# Invictus_R2_Bot.net
KiCad netlist of a schematic drawn in EAGLE
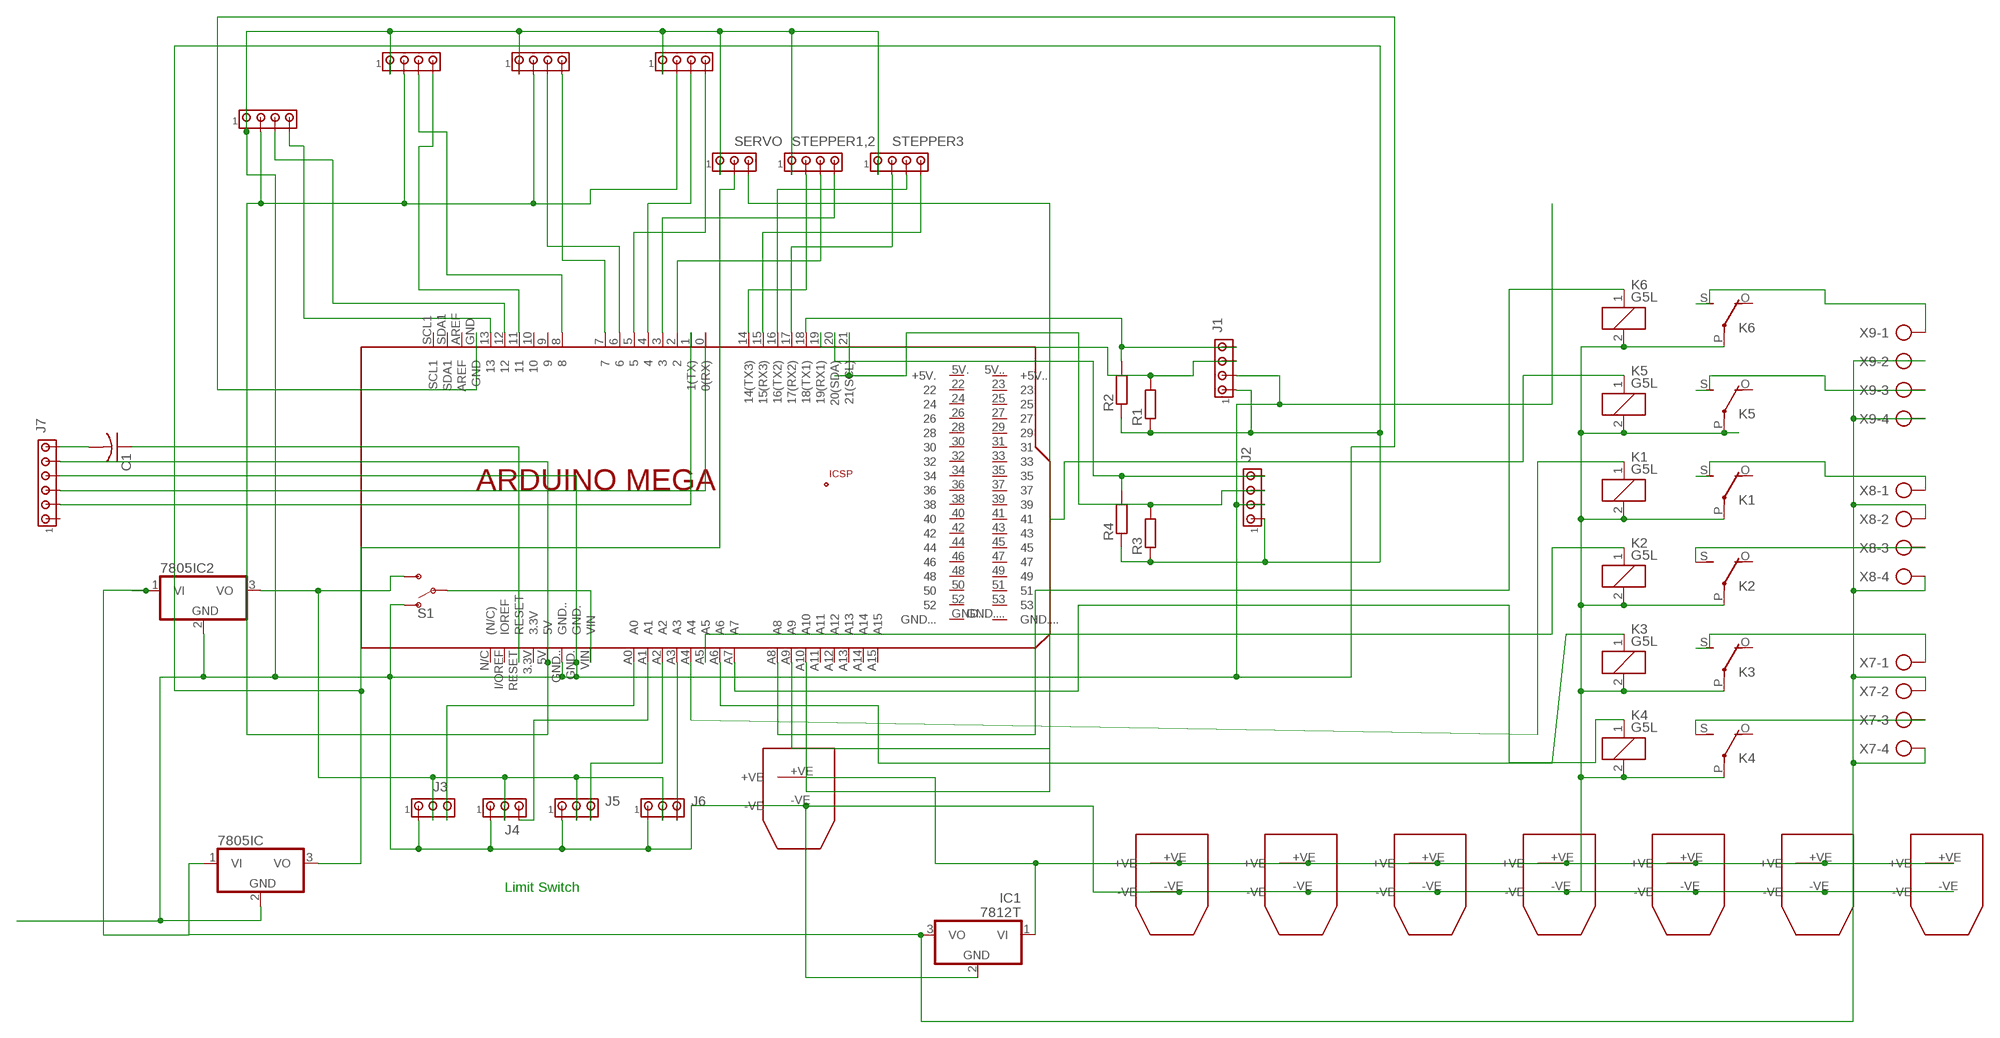
[diagram p0: schematic, sheet 1]

(export (version "E")
  (design (tool "Eeschema 10.0.6"))
  (components
    (comp (ref "7805IC")
      (value "7812T")
      (footprint "eagle-import:TO220H")
      (libsource (lib "eagle-import") (part "78T12"))
    )
    (comp (ref "7805IC2")
      (value "7805T")
      (footprint "eagle-import:TO220H")
      (libsource (lib "eagle-import") (part "78T05"))
    )
    (comp (ref "C1")
      (value "C-US025-030X050")
      (footprint "eagle-import:C025-030X050")
      (libsource (lib "eagle-import") (part "C-US025-030X050"))
    )
    (comp (ref "IC1")
      (value "7812T")
      (footprint "eagle-import:TO220H")
      (libsource (lib "eagle-import") (part "78T12"))
    )
    (comp (ref "J1")
      (value "MTA04-100")
      (footprint "eagle-import:10X04MTA")
      (libsource (lib "eagle-import") (part "MTA04-100"))
    )
    (comp (ref "J2")
      (value "MTA04-100")
      (footprint "eagle-import:10X04MTA")
      (libsource (lib "eagle-import") (part "MTA04-100"))
    )
    (comp (ref "J3")
      (value "MTA03-100")
      (footprint "eagle-import:10X03MTA")
      (libsource (lib "eagle-import") (part "MTA03-100"))
    )
    (comp (ref "J4")
      (value "MTA03-100")
      (footprint "eagle-import:10X03MTA")
      (libsource (lib "eagle-import") (part "MTA03-100"))
    )
    (comp (ref "J5")
      (value "MTA03-100")
      (footprint "eagle-import:10X03MTA")
      (libsource (lib "eagle-import") (part "MTA03-100"))
    )
    (comp (ref "J6")
      (value "MTA03-100")
      (footprint "eagle-import:10X03MTA")
      (libsource (lib "eagle-import") (part "MTA03-100"))
    )
    (comp (ref "J7")
      (value "MTA06-100")
      (footprint "eagle-import:10X06MTA")
      (libsource (lib "eagle-import") (part "MTA06-100"))
    )
    (comp (ref "K1")
      (value "G5L")
      (footprint "eagle-import:G5LE")
      (libsource (lib "eagle-import") (part "G5L"))
    )
    (comp (ref "K2")
      (value "G5L")
      (footprint "eagle-import:G5LE")
      (libsource (lib "eagle-import") (part "G5L"))
    )
    (comp (ref "K3")
      (value "G5L")
      (footprint "eagle-import:G5LE")
      (libsource (lib "eagle-import") (part "G5L"))
    )
    (comp (ref "K4")
      (value "G5L")
      (footprint "eagle-import:G5LE")
      (libsource (lib "eagle-import") (part "G5L"))
    )
    (comp (ref "K5")
      (value "G5L")
      (footprint "eagle-import:G5LE")
      (libsource (lib "eagle-import") (part "G5L"))
    )
    (comp (ref "K6")
      (value "G5L")
      (footprint "eagle-import:G5LE")
      (libsource (lib "eagle-import") (part "G5L"))
    )
    (comp (ref "PCB2")
      (value "ARDUINO_MEGA2560")
      (footprint "eagle-import:ARDUINO_MEGA2560")
      (libsource (lib "eagle-import") (part "ARDUINO_MEGA2560"))
    )
    (comp (ref "R1")
      (value "R-EU_0207/7")
      (footprint "eagle-import:0207_7")
      (libsource (lib "eagle-import") (part "R-EU_0207/7"))
    )
    (comp (ref "R2")
      (value "R-EU_0207/7")
      (footprint "eagle-import:0207_7")
      (libsource (lib "eagle-import") (part "R-EU_0207/7"))
    )
    (comp (ref "R3")
      (value "R-EU_0207/7")
      (footprint "eagle-import:0207_7")
      (libsource (lib "eagle-import") (part "R-EU_0207/7"))
    )
    (comp (ref "R4")
      (value "R-EU_0207/7")
      (footprint "eagle-import:0207_7")
      (libsource (lib "eagle-import") (part "R-EU_0207/7"))
    )
    (comp (ref "S1")
      (value "SWITCH-SPDT-PTH-11.6X4.0MM")
      (footprint "eagle-import:SWITCH_SPDT_PTH_11.6X4.0MM")
      (libsource (lib "eagle-import") (part "SWITCH-SPDT-PTH-11.6X4.0MM"))
    )
    (comp (ref "SERVO")
      (value "MTA03-100")
      (footprint "eagle-import:10X03MTA")
      (libsource (lib "eagle-import") (part "MTA03-100"))
    )
    (comp (ref "STEPPER1,1")
      (value "MTA04-100")
      (footprint "eagle-import:10X04MTA")
      (libsource (lib "eagle-import") (part "MTA04-100"))
    )
    (comp (ref "STEPPER1,2")
      (value "MTA04-100")
      (footprint "eagle-import:10X04MTA")
      (libsource (lib "eagle-import") (part "MTA04-100"))
    )
    (comp (ref "STEPPER1,3")
      (value "MTA04-100")
      (footprint "eagle-import:10X04MTA")
      (libsource (lib "eagle-import") (part "MTA04-100"))
    )
    (comp (ref "STEPPER1,4")
      (value "MTA04-100")
      (footprint "eagle-import:10X04MTA")
      (libsource (lib "eagle-import") (part "MTA04-100"))
    )
    (comp (ref "STEPPER1,5")
      (value "MTA04-100")
      (footprint "eagle-import:10X04MTA")
      (libsource (lib "eagle-import") (part "MTA04-100"))
    )
    (comp (ref "STEPPER3")
      (value "MTA04-100")
      (footprint "eagle-import:10X04MTA")
      (libsource (lib "eagle-import") (part "MTA04-100"))
    )
    (comp (ref "X7")
      (value "AK500/4-H")
      (footprint "eagle-import:AK500_4-H")
      (libsource (lib "eagle-import") (part "AK500/4-H"))
    )
    (comp (ref "X8")
      (value "AK500/4-H")
      (footprint "eagle-import:AK500_4-H")
      (libsource (lib "eagle-import") (part "AK500/4-H"))
    )
    (comp (ref "X9")
      (value "AK500/4-H")
      (footprint "eagle-import:AK500_4-H")
      (libsource (lib "eagle-import") (part "AK500/4-H"))
    )
    (comp (ref "XT1")
      (value "XT60XT60")
      (footprint "eagle-import:XT60")
      (libsource (lib "eagle-import") (part "XT60XT60"))
    )
    (comp (ref "XT2")
      (value "XT60XT60")
      (footprint "eagle-import:XT60")
      (libsource (lib "eagle-import") (part "XT60XT60"))
    )
    (comp (ref "XT3")
      (value "XT60XT60")
      (footprint "eagle-import:XT60")
      (libsource (lib "eagle-import") (part "XT60XT60"))
    )
    (comp (ref "XT4")
      (value "XT60XT60")
      (footprint "eagle-import:XT60")
      (libsource (lib "eagle-import") (part "XT60XT60"))
    )
    (comp (ref "XT5")
      (value "XT60XT60")
      (footprint "eagle-import:XT60")
      (libsource (lib "eagle-import") (part "XT60XT60"))
    )
    (comp (ref "XT6")
      (value "XT60XT60")
      (footprint "eagle-import:XT60")
      (libsource (lib "eagle-import") (part "XT60XT60"))
    )
    (comp (ref "XT7")
      (value "XT60XT60")
      (footprint "eagle-import:XT60")
      (libsource (lib "eagle-import") (part "XT60XT60"))
    )
    (comp (ref "XT60")
      (value "XT60XT60")
      (footprint "eagle-import:XT60")
      (libsource (lib "eagle-import") (part "XT60XT60"))
    )
  )
  (nets
    (net (code "1") (name "Net-(7805IC-GND)") (class "Default")
      (node (ref "7805IC") (pin "2") (pinfunction "GND_2") (pintype "passive"))
      (node (ref "7805IC2") (pin "2") (pinfunction "GND_2") (pintype "passive"))
      (node (ref "IC1") (pin "2") (pinfunction "GND_2") (pintype "passive"))
      (node (ref "J1") (pin "2") (pinfunction "2_2") (pintype "passive"))
      (node (ref "J2") (pin "2") (pinfunction "2_2") (pintype "passive"))
      (node (ref "J3") (pin "1") (pinfunction "1_1") (pintype "passive"))
      (node (ref "J4") (pin "1") (pinfunction "1_1") (pintype "passive"))
      (node (ref "J5") (pin "1") (pinfunction "1_1") (pintype "passive"))
      (node (ref "J6") (pin "1") (pinfunction "1_1") (pintype "passive"))
      (node (ref "J7") (pin "4") (pinfunction "4_4") (pintype "passive"))
      (node (ref "K1") (pin "2") (pinfunction "2_2") (pintype "passive"))
      (node (ref "K1") (pin "P") (pinfunction "P_P") (pintype "passive"))
      (node (ref "K2") (pin "2") (pinfunction "2_2") (pintype "passive"))
      (node (ref "K2") (pin "P") (pinfunction "P_P") (pintype "passive"))
      (node (ref "K3") (pin "2") (pinfunction "2_2") (pintype "passive"))
      (node (ref "K3") (pin "P") (pinfunction "P_P") (pintype "passive"))
      (node (ref "K4") (pin "2") (pinfunction "2_2") (pintype "passive"))
      (node (ref "K4") (pin "P") (pinfunction "P_P") (pintype "passive"))
      (node (ref "K5") (pin "2") (pinfunction "2_2") (pintype "passive"))
      (node (ref "K5") (pin "P") (pinfunction "P_P") (pintype "passive"))
      (node (ref "K6") (pin "2") (pinfunction "2_2") (pintype "passive"))
      (node (ref "K6") (pin "P") (pinfunction "P_P") (pintype "passive"))
      (node (ref "PCB2") (pin "GND") (pinfunction "GND_GND") (pintype "bidirectional"))
      (node (ref "PCB2") (pin "GND.") (pinfunction "GND._GND.") (pintype "bidirectional"))
      (node (ref "PCB2") (pin "GND..") (pinfunction "GND.._GND..") (pintype "bidirectional"))
      (node (ref "S1") (pin "1") (pinfunction "O_1") (pintype "passive"))
      (node (ref "SERVO") (pin "1") (pinfunction "1_1") (pintype "passive"))
      (node (ref "STEPPER1,1") (pin "1") (pinfunction "1_1") (pintype "passive"))
      (node (ref "STEPPER1,2") (pin "1") (pinfunction "1_1") (pintype "passive"))
      (node (ref "STEPPER1,3") (pin "1") (pinfunction "1_1") (pintype "passive"))
      (node (ref "STEPPER1,4") (pin "1") (pinfunction "1_1") (pintype "passive"))
      (node (ref "STEPPER1,5") (pin "1") (pinfunction "1_1") (pintype "passive"))
      (node (ref "STEPPER3") (pin "1") (pinfunction "1_1") (pintype "passive"))
      (node (ref "XT1") (pin "-VE") (pinfunction "-VE_-VE") (pintype "bidirectional"))
      (node (ref "XT2") (pin "-VE") (pinfunction "-VE_-VE") (pintype "bidirectional"))
      (node (ref "XT3") (pin "-VE") (pinfunction "-VE_-VE") (pintype "bidirectional"))
      (node (ref "XT4") (pin "-VE") (pinfunction "-VE_-VE") (pintype "bidirectional"))
      (node (ref "XT5") (pin "-VE") (pinfunction "-VE_-VE") (pintype "bidirectional"))
      (node (ref "XT6") (pin "-VE") (pinfunction "-VE_-VE") (pintype "bidirectional"))
      (node (ref "XT60") (pin "-VE") (pinfunction "-VE_-VE") (pintype "bidirectional"))
      (node (ref "XT7") (pin "-VE") (pinfunction "-VE_-VE") (pintype "bidirectional"))
    )
    (net (code "2") (name "Net-(7805IC-VI)") (class "Default")
      (node (ref "7805IC") (pin "1") (pinfunction "VI_1") (pintype "input"))
      (node (ref "7805IC2") (pin "1") (pinfunction "VI_1") (pintype "input"))
      (node (ref "IC1") (pin "3") (pinfunction "VO_3") (pintype "passive"))
      (node (ref "X7") (pin "2") (pinfunction "KL_2") (pintype "passive"))
      (node (ref "X7") (pin "4") (pinfunction "KL_4") (pintype "passive"))
      (node (ref "X8") (pin "2") (pinfunction "KL_2") (pintype "passive"))
      (node (ref "X8") (pin "4") (pinfunction "KL_4") (pintype "passive"))
      (node (ref "X9") (pin "2") (pinfunction "KL_2") (pintype "passive"))
      (node (ref "X9") (pin "4") (pinfunction "KL_4") (pintype "passive"))
    )
    (net (code "3") (name "Net-(7805IC-VO)") (class "Default")
      (node (ref "7805IC") (pin "3") (pinfunction "VO_3") (pintype "passive"))
      (node (ref "J1") (pin "1") (pinfunction "1_1") (pintype "passive"))
      (node (ref "J2") (pin "1") (pinfunction "1_1") (pintype "passive"))
      (node (ref "R1") (pin "1") (pinfunction "1_1") (pintype "passive"))
      (node (ref "R2") (pin "1") (pinfunction "1_1") (pintype "passive"))
      (node (ref "R3") (pin "1") (pinfunction "1_1") (pintype "passive"))
      (node (ref "R4") (pin "1") (pinfunction "1_1") (pintype "passive"))
      (node (ref "SERVO") (pin "2") (pinfunction "2_2") (pintype "passive"))
    )
    (net (code "4") (name "Net-(7805IC2-VO)") (class "Default")
      (node (ref "7805IC2") (pin "3") (pinfunction "VO_3") (pintype "passive"))
      (node (ref "J3") (pin "2") (pinfunction "2_2") (pintype "passive"))
      (node (ref "J4") (pin "2") (pinfunction "2_2") (pintype "passive"))
      (node (ref "J5") (pin "2") (pinfunction "2_2") (pintype "passive"))
      (node (ref "J6") (pin "2") (pinfunction "2_2") (pintype "passive"))
      (node (ref "S1") (pin "3") (pinfunction "S_3") (pintype "passive"))
    )
    (net (code "5") (name "Net-(C1-Pad1)") (class "Default")
      (node (ref "C1") (pin "1") (pinfunction "1_1") (pintype "passive"))
      (node (ref "PCB2") (pin "RESET") (pinfunction "RESET_RESET") (pintype "bidirectional"))
    )
    (net (code "6") (name "Net-(C1-Pad2)") (class "Default")
      (node (ref "C1") (pin "2") (pinfunction "2_2") (pintype "passive"))
      (node (ref "J7") (pin "6") (pinfunction "6_6") (pintype "passive"))
    )
    (net (code "7") (name "Net-(IC1-VI)") (class "Default")
      (node (ref "IC1") (pin "1") (pinfunction "VI_1") (pintype "input"))
      (node (ref "XT1") (pin "+VE") (pinfunction "+VE_+VE") (pintype "bidirectional"))
      (node (ref "XT2") (pin "+VE") (pinfunction "+VE_+VE") (pintype "bidirectional"))
      (node (ref "XT3") (pin "+VE") (pinfunction "+VE_+VE") (pintype "bidirectional"))
      (node (ref "XT4") (pin "+VE") (pinfunction "+VE_+VE") (pintype "bidirectional"))
      (node (ref "XT5") (pin "+VE") (pinfunction "+VE_+VE") (pintype "bidirectional"))
      (node (ref "XT6") (pin "+VE") (pinfunction "+VE_+VE") (pintype "bidirectional"))
      (node (ref "XT60") (pin "+VE") (pinfunction "+VE_+VE") (pintype "bidirectional"))
      (node (ref "XT7") (pin "+VE") (pinfunction "+VE_+VE") (pintype "bidirectional"))
    )
    (net (code "8") (name "Net-(J3-Pad3)") (class "Default")
      (node (ref "J3") (pin "3") (pinfunction "3_3") (pintype "passive"))
      (node (ref "PCB2") (pin "A0") (pinfunction "A0_A0") (pintype "bidirectional"))
    )
    (net (code "9") (name "Net-(J4-Pad3)") (class "Default")
      (node (ref "J4") (pin "3") (pinfunction "3_3") (pintype "passive"))
      (node (ref "PCB2") (pin "A1") (pinfunction "A1_A1") (pintype "bidirectional"))
    )
    (net (code "10") (name "Net-(J5-Pad3)") (class "Default")
      (node (ref "J5") (pin "3") (pinfunction "3_3") (pintype "passive"))
      (node (ref "PCB2") (pin "A2") (pinfunction "A2_A2") (pintype "bidirectional"))
    )
    (net (code "11") (name "Net-(J6-Pad3)") (class "Default")
      (node (ref "J6") (pin "3") (pinfunction "3_3") (pintype "passive"))
      (node (ref "PCB2") (pin "A3") (pinfunction "A3_A3") (pintype "bidirectional"))
    )
    (net (code "12") (name "Net-(J7-Pad5)") (class "Default")
      (node (ref "J7") (pin "5") (pinfunction "5_5") (pintype "passive"))
      (node (ref "PCB2") (pin "5V") (pinfunction "5V_5V") (pintype "bidirectional"))
      (node (ref "STEPPER1,1") (pin "2") (pinfunction "2_2") (pintype "passive"))
      (node (ref "STEPPER1,3") (pin "2") (pinfunction "2_2") (pintype "passive"))
      (node (ref "STEPPER1,4") (pin "2") (pinfunction "2_2") (pintype "passive"))
      (node (ref "STEPPER1,5") (pin "2") (pinfunction "2_2") (pintype "passive"))
    )
    (net (code "13") (name "Net-(K1-Pad1)") (class "Default")
      (node (ref "K1") (pin "1") (pinfunction "1_1") (pintype "passive"))
      (node (ref "PCB2") (pin "A4") (pinfunction "A4_A4") (pintype "bidirectional"))
    )
    (net (code "14") (name "Net-(K2-Pad1)") (class "Default")
      (node (ref "K2") (pin "1") (pinfunction "1_1") (pintype "passive"))
      (node (ref "PCB2") (pin "A5") (pinfunction "A5_A5") (pintype "bidirectional"))
    )
    (net (code "15") (name "Net-(K3-Pad1)") (class "Default")
      (node (ref "K3") (pin "1") (pinfunction "1_1") (pintype "passive"))
      (node (ref "PCB2") (pin "A6") (pinfunction "A6_A6") (pintype "bidirectional"))
    )
    (net (code "16") (name "Net-(K4-Pad1)") (class "Default")
      (node (ref "K4") (pin "1") (pinfunction "1_1") (pintype "passive"))
      (node (ref "PCB2") (pin "A7") (pinfunction "A7_A7") (pintype "bidirectional"))
    )
    (net (code "17") (name "Net-(K5-Pad1)") (class "Default")
      (node (ref "K5") (pin "1") (pinfunction "1_1") (pintype "passive"))
      (node (ref "PCB2") (pin "A9") (pinfunction "A9_A9") (pintype "bidirectional"))
    )
    (net (code "18") (name "Net-(K6-Pad1)") (class "Default")
      (node (ref "K6") (pin "1") (pinfunction "1_1") (pintype "passive"))
      (node (ref "PCB2") (pin "A8") (pinfunction "A8_A8") (pintype "bidirectional"))
    )
    (net (code "19") (name "Net-(PCB2-0(RX))") (class "Default")
      (node (ref "J7") (pin "3") (pinfunction "3_3") (pintype "passive"))
      (node (ref "PCB2") (pin "0") (pinfunction "0(RX)_0") (pintype "bidirectional"))
    )
    (net (code "20") (name "Net-(PCB2-1(TX))") (class "Default")
      (node (ref "J7") (pin "2") (pinfunction "2_2") (pintype "passive"))
      (node (ref "PCB2") (pin "1") (pinfunction "1(TX)_1") (pintype "bidirectional"))
    )
    (net (code "21") (name "Net-(PCB2-14(TX3))") (class "Default")
      (node (ref "PCB2") (pin "14") (pinfunction "14(TX3)_14") (pintype "bidirectional"))
      (node (ref "STEPPER1,2") (pin "2") (pinfunction "2_2") (pintype "passive"))
    )
    (net (code "22") (name "Net-(PCB2-15(RX3))") (class "Default")
      (node (ref "PCB2") (pin "15") (pinfunction "15(RX3)_15") (pintype "bidirectional"))
      (node (ref "STEPPER3") (pin "4") (pinfunction "4_4") (pintype "passive"))
    )
    (net (code "23") (name "Net-(PCB2-16(TX2))") (class "Default")
      (node (ref "PCB2") (pin "16") (pinfunction "16(TX2)_16") (pintype "bidirectional"))
      (node (ref "STEPPER3") (pin "3") (pinfunction "3_3") (pintype "passive"))
    )
    (net (code "24") (name "Net-(PCB2-17(RX2))") (class "Default")
      (node (ref "PCB2") (pin "17") (pinfunction "17(RX2)_17") (pintype "bidirectional"))
      (node (ref "STEPPER3") (pin "2") (pinfunction "2_2") (pintype "passive"))
    )
    (net (code "25") (name "Net-(PCB2-18(TX1))") (class "Default")
      (node (ref "J1") (pin "4") (pinfunction "4_4") (pintype "passive"))
      (node (ref "PCB2") (pin "18") (pinfunction "18(TX1)_18") (pintype "bidirectional"))
      (node (ref "R2") (pin "2") (pinfunction "2_2") (pintype "passive"))
    )
    (net (code "26") (name "Net-(PCB2-19(RX1))") (class "Default")
      (node (ref "J1") (pin "3") (pinfunction "3_3") (pintype "passive"))
      (node (ref "PCB2") (pin "19") (pinfunction "19(RX1)_19") (pintype "bidirectional"))
      (node (ref "R1") (pin "2") (pinfunction "2_2") (pintype "passive"))
    )
    (net (code "27") (name "Net-(PCB2-20(SDA))") (class "Default")
      (node (ref "J2") (pin "4") (pinfunction "4_4") (pintype "passive"))
      (node (ref "PCB2") (pin "20") (pinfunction "20(SDA)_20") (pintype "bidirectional"))
      (node (ref "R4") (pin "2") (pinfunction "2_2") (pintype "passive"))
    )
    (net (code "28") (name "Net-(PCB2-21(SCL))") (class "Default")
      (node (ref "J2") (pin "3") (pinfunction "3_3") (pintype "passive"))
      (node (ref "PCB2") (pin "21") (pinfunction "21(SCL)_21") (pintype "bidirectional"))
      (node (ref "R3") (pin "2") (pinfunction "2_2") (pintype "passive"))
    )
    (net (code "29") (name "Net-(PCB2-Pad2)") (class "Default")
      (node (ref "PCB2") (pin "2") (pinfunction "2_2") (pintype "bidirectional"))
      (node (ref "STEPPER1,2") (pin "3") (pinfunction "3_3") (pintype "passive"))
    )
    (net (code "30") (name "Net-(PCB2-Pad3)") (class "Default")
      (node (ref "PCB2") (pin "3") (pinfunction "3_3") (pintype "bidirectional"))
      (node (ref "STEPPER1,2") (pin "4") (pinfunction "4_4") (pintype "passive"))
    )
    (net (code "31") (name "Net-(PCB2-Pad4)") (class "Default")
      (node (ref "PCB2") (pin "4") (pinfunction "4_4") (pintype "bidirectional"))
      (node (ref "STEPPER1,5") (pin "3") (pinfunction "3_3") (pintype "passive"))
    )
    (net (code "32") (name "Net-(PCB2-Pad5)") (class "Default")
      (node (ref "PCB2") (pin "5") (pinfunction "5_5") (pintype "bidirectional"))
      (node (ref "STEPPER1,5") (pin "4") (pinfunction "4_4") (pintype "passive"))
    )
    (net (code "33") (name "Net-(PCB2-Pad6)") (class "Default")
      (node (ref "PCB2") (pin "6") (pinfunction "6_6") (pintype "bidirectional"))
      (node (ref "STEPPER1,4") (pin "3") (pinfunction "3_3") (pintype "passive"))
    )
    (net (code "34") (name "Net-(PCB2-Pad7)") (class "Default")
      (node (ref "PCB2") (pin "7") (pinfunction "7_7") (pintype "bidirectional"))
      (node (ref "STEPPER1,4") (pin "4") (pinfunction "4_4") (pintype "passive"))
    )
    (net (code "35") (name "Net-(PCB2-Pad8)") (class "Default")
      (node (ref "PCB2") (pin "8") (pinfunction "8_8") (pintype "bidirectional"))
      (node (ref "STEPPER1,3") (pin "3") (pinfunction "3_3") (pintype "passive"))
    )
    (net (code "36") (name "Net-(PCB2-Pad11)") (class "Default")
      (node (ref "PCB2") (pin "11") (pinfunction "11_11") (pintype "bidirectional"))
      (node (ref "STEPPER1,3") (pin "4") (pinfunction "4_4") (pintype "passive"))
    )
    (net (code "37") (name "Net-(PCB2-Pad12)") (class "Default")
      (node (ref "PCB2") (pin "12") (pinfunction "12_12") (pintype "bidirectional"))
      (node (ref "STEPPER1,1") (pin "3") (pinfunction "3_3") (pintype "passive"))
    )
    (net (code "38") (name "Net-(PCB2-Pad13)") (class "Default")
      (node (ref "PCB2") (pin "13") (pinfunction "13_13") (pintype "bidirectional"))
      (node (ref "STEPPER1,1") (pin "4") (pinfunction "4_4") (pintype "passive"))
    )
    (net (code "39") (name "Net-(PCB2-PadA10)") (class "Default")
      (node (ref "PCB2") (pin "A10") (pinfunction "A10_A10") (pintype "bidirectional"))
      (node (ref "SERVO") (pin "3") (pinfunction "3_3") (pintype "passive"))
    )
    (net (code "40") (name "Net-(S1-P)") (class "Default")
      (node (ref "PCB2") (pin "VIN") (pinfunction "VIN_VIN") (pintype "bidirectional"))
      (node (ref "S1") (pin "2") (pinfunction "P_2") (pintype "passive"))
    )
    (net (code "41") (name "Net-(X7A-KL)") (class "Default")
      (node (ref "K3") (pin "S") (pinfunction "S_S") (pintype "passive"))
      (node (ref "X7") (pin "1") (pinfunction "KL_1") (pintype "passive"))
    )
    (net (code "42") (name "Net-(X7C-KL)") (class "Default")
      (node (ref "K4") (pin "S") (pinfunction "S_S") (pintype "passive"))
      (node (ref "X7") (pin "3") (pinfunction "KL_3") (pintype "passive"))
    )
    (net (code "43") (name "Net-(X8A-KL)") (class "Default")
      (node (ref "K1") (pin "S") (pinfunction "S_S") (pintype "passive"))
      (node (ref "X8") (pin "1") (pinfunction "KL_1") (pintype "passive"))
    )
    (net (code "44") (name "Net-(X8C-KL)") (class "Default")
      (node (ref "K2") (pin "S") (pinfunction "S_S") (pintype "passive"))
      (node (ref "X8") (pin "3") (pinfunction "KL_3") (pintype "passive"))
    )
    (net (code "45") (name "Net-(X9A-KL)") (class "Default")
      (node (ref "K6") (pin "S") (pinfunction "S_S") (pintype "passive"))
      (node (ref "X9") (pin "1") (pinfunction "KL_1") (pintype "passive"))
    )
    (net (code "46") (name "Net-(X9C-KL)") (class "Default")
      (node (ref "K5") (pin "S") (pinfunction "S_S") (pintype "passive"))
      (node (ref "X9") (pin "3") (pinfunction "KL_3") (pintype "passive"))
    )
    (net (code "47") (name "unconnected-(J7-Pad1)") (class "Default")
      (node (ref "J7") (pin "1") (pinfunction "1_1") (pintype "passive"))
    )
    (net (code "48") (name "unconnected-(K1-PadO)") (class "Default")
      (node (ref "K1") (pin "O") (pinfunction "O_O") (pintype "passive"))
    )
    (net (code "49") (name "unconnected-(K2-PadO)") (class "Default")
      (node (ref "K2") (pin "O") (pinfunction "O_O") (pintype "passive"))
    )
    (net (code "50") (name "unconnected-(K3-PadO)") (class "Default")
      (node (ref "K3") (pin "O") (pinfunction "O_O") (pintype "passive"))
    )
    (net (code "51") (name "unconnected-(K4-PadO)") (class "Default")
      (node (ref "K4") (pin "O") (pinfunction "O_O") (pintype "passive"))
    )
    (net (code "52") (name "unconnected-(K5-PadO)") (class "Default")
      (node (ref "K5") (pin "O") (pinfunction "O_O") (pintype "passive"))
    )
    (net (code "53") (name "unconnected-(K6-PadO)") (class "Default")
      (node (ref "K6") (pin "O") (pinfunction "O_O") (pintype "passive"))
    )
    (net (code "54") (name "unconnected-(PCB2-(N{slash}C)-PadN{slash}C)") (class "Default")
      (node (ref "PCB2") (pin "N/C") (pinfunction "(N/C)_N/C") (pintype "bidirectional"))
    )
    (net (code "55") (name "unconnected-(PCB2-+5V.-Pad5V.)") (class "Default")
      (node (ref "PCB2") (pin "5V.") (pinfunction "+5V._5V.") (pintype "bidirectional"))
    )
    (net (code "56") (name "unconnected-(PCB2-+5V..-Pad5V..)") (class "Default")
      (node (ref "PCB2") (pin "5V..") (pinfunction "+5V.._5V..") (pintype "bidirectional"))
    )
    (net (code "57") (name "unconnected-(PCB2-IOREF-PadI{slash}OREF)") (class "Default")
      (node (ref "PCB2") (pin "I/OREF") (pinfunction "IOREF_I/OREF") (pintype "bidirectional"))
    )
    (net (code "58") (name "unconnected-(PCB2-Pad+5V_)") (class "Default")
      (node (ref "PCB2") (pin "+5V_") (pinfunction "+5V__+5V_") (pintype "bidirectional"))
    )
    (net (code "59") (name "unconnected-(PCB2-Pad3.3V)") (class "Default")
      (node (ref "PCB2") (pin "3.3V") (pinfunction "3.3V_3.3V") (pintype "bidirectional"))
    )
    (net (code "60") (name "unconnected-(PCB2-Pad9)") (class "Default")
      (node (ref "PCB2") (pin "9") (pinfunction "9_9") (pintype "bidirectional"))
    )
    (net (code "61") (name "unconnected-(PCB2-Pad10)") (class "Default")
      (node (ref "PCB2") (pin "10") (pinfunction "10_10") (pintype "bidirectional"))
    )
    (net (code "62") (name "unconnected-(PCB2-Pad22)") (class "Default")
      (node (ref "PCB2") (pin "22") (pinfunction "22_22") (pintype "bidirectional"))
    )
    (net (code "63") (name "unconnected-(PCB2-Pad23)") (class "Default")
      (node (ref "PCB2") (pin "23") (pinfunction "23_23") (pintype "bidirectional"))
    )
    (net (code "64") (name "unconnected-(PCB2-Pad24)") (class "Default")
      (node (ref "PCB2") (pin "24") (pinfunction "24_24") (pintype "bidirectional"))
    )
    (net (code "65") (name "unconnected-(PCB2-Pad25)") (class "Default")
      (node (ref "PCB2") (pin "25") (pinfunction "25_25") (pintype "bidirectional"))
    )
    (net (code "66") (name "unconnected-(PCB2-Pad26)") (class "Default")
      (node (ref "PCB2") (pin "26") (pinfunction "26_26") (pintype "bidirectional"))
    )
    (net (code "67") (name "unconnected-(PCB2-Pad27)") (class "Default")
      (node (ref "PCB2") (pin "27") (pinfunction "27_27") (pintype "bidirectional"))
    )
    (net (code "68") (name "unconnected-(PCB2-Pad28)") (class "Default")
      (node (ref "PCB2") (pin "28") (pinfunction "28_28") (pintype "bidirectional"))
    )
    (net (code "69") (name "unconnected-(PCB2-Pad29)") (class "Default")
      (node (ref "PCB2") (pin "29") (pinfunction "29_29") (pintype "bidirectional"))
    )
    (net (code "70") (name "unconnected-(PCB2-Pad30)") (class "Default")
      (node (ref "PCB2") (pin "30") (pinfunction "30_30") (pintype "bidirectional"))
    )
    (net (code "71") (name "unconnected-(PCB2-Pad31)") (class "Default")
      (node (ref "PCB2") (pin "31") (pinfunction "31_31") (pintype "bidirectional"))
    )
    (net (code "72") (name "unconnected-(PCB2-Pad32)") (class "Default")
      (node (ref "PCB2") (pin "32") (pinfunction "32_32") (pintype "bidirectional"))
    )
    (net (code "73") (name "unconnected-(PCB2-Pad33)") (class "Default")
      (node (ref "PCB2") (pin "33") (pinfunction "33_33") (pintype "bidirectional"))
    )
    (net (code "74") (name "unconnected-(PCB2-Pad34)") (class "Default")
      (node (ref "PCB2") (pin "34") (pinfunction "34_34") (pintype "bidirectional"))
    )
    (net (code "75") (name "unconnected-(PCB2-Pad35)") (class "Default")
      (node (ref "PCB2") (pin "35") (pinfunction "35_35") (pintype "bidirectional"))
    )
    (net (code "76") (name "unconnected-(PCB2-Pad36)") (class "Default")
      (node (ref "PCB2") (pin "36") (pinfunction "36_36") (pintype "bidirectional"))
    )
    (net (code "77") (name "unconnected-(PCB2-Pad37)") (class "Default")
      (node (ref "PCB2") (pin "37") (pinfunction "37_37") (pintype "bidirectional"))
    )
    (net (code "78") (name "unconnected-(PCB2-Pad38)") (class "Default")
      (node (ref "PCB2") (pin "38") (pinfunction "38_38") (pintype "bidirectional"))
    )
    (net (code "79") (name "unconnected-(PCB2-Pad39)") (class "Default")
      (node (ref "PCB2") (pin "39") (pinfunction "39_39") (pintype "bidirectional"))
    )
    (net (code "80") (name "unconnected-(PCB2-Pad40)") (class "Default")
      (node (ref "PCB2") (pin "40") (pinfunction "40_40") (pintype "bidirectional"))
    )
    (net (code "81") (name "unconnected-(PCB2-Pad41)") (class "Default")
      (node (ref "PCB2") (pin "41") (pinfunction "41_41") (pintype "bidirectional"))
    )
    (net (code "82") (name "unconnected-(PCB2-Pad42)") (class "Default")
      (node (ref "PCB2") (pin "42") (pinfunction "42_42") (pintype "bidirectional"))
    )
    (net (code "83") (name "unconnected-(PCB2-Pad43)") (class "Default")
      (node (ref "PCB2") (pin "43") (pinfunction "43_43") (pintype "bidirectional"))
    )
    (net (code "84") (name "unconnected-(PCB2-Pad44)") (class "Default")
      (node (ref "PCB2") (pin "44") (pinfunction "44_44") (pintype "bidirectional"))
    )
    (net (code "85") (name "unconnected-(PCB2-Pad45)") (class "Default")
      (node (ref "PCB2") (pin "45") (pinfunction "45_45") (pintype "bidirectional"))
    )
    (net (code "86") (name "unconnected-(PCB2-Pad46)") (class "Default")
      (node (ref "PCB2") (pin "46") (pinfunction "46_46") (pintype "bidirectional"))
    )
    (net (code "87") (name "unconnected-(PCB2-Pad47)") (class "Default")
      (node (ref "PCB2") (pin "47") (pinfunction "47_47") (pintype "bidirectional"))
    )
    (net (code "88") (name "unconnected-(PCB2-Pad48)") (class "Default")
      (node (ref "PCB2") (pin "48") (pinfunction "48_48") (pintype "bidirectional"))
    )
    (net (code "89") (name "unconnected-(PCB2-Pad49)") (class "Default")
      (node (ref "PCB2") (pin "49") (pinfunction "49_49") (pintype "bidirectional"))
    )
    (net (code "90") (name "unconnected-(PCB2-Pad50)") (class "Default")
      (node (ref "PCB2") (pin "50") (pinfunction "50_50") (pintype "bidirectional"))
    )
    (net (code "91") (name "unconnected-(PCB2-Pad51)") (class "Default")
      (node (ref "PCB2") (pin "51") (pinfunction "51_51") (pintype "bidirectional"))
    )
    (net (code "92") (name "unconnected-(PCB2-Pad52)") (class "Default")
      (node (ref "PCB2") (pin "52") (pinfunction "52_52") (pintype "bidirectional"))
    )
    (net (code "93") (name "unconnected-(PCB2-Pad53)") (class "Default")
      (node (ref "PCB2") (pin "53") (pinfunction "53_53") (pintype "bidirectional"))
    )
    (net (code "94") (name "unconnected-(PCB2-PadA11)") (class "Default")
      (node (ref "PCB2") (pin "A11") (pinfunction "A11_A11") (pintype "bidirectional"))
    )
    (net (code "95") (name "unconnected-(PCB2-PadA12)") (class "Default")
      (node (ref "PCB2") (pin "A12") (pinfunction "A12_A12") (pintype "bidirectional"))
    )
    (net (code "96") (name "unconnected-(PCB2-PadA13)") (class "Default")
      (node (ref "PCB2") (pin "A13") (pinfunction "A13_A13") (pintype "bidirectional"))
    )
    (net (code "97") (name "unconnected-(PCB2-PadA14)") (class "Default")
      (node (ref "PCB2") (pin "A14") (pinfunction "A14_A14") (pintype "bidirectional"))
    )
    (net (code "98") (name "unconnected-(PCB2-PadA15)") (class "Default")
      (node (ref "PCB2") (pin "A15") (pinfunction "A15_A15") (pintype "bidirectional"))
    )
    (net (code "99") (name "unconnected-(PCB2-PadAREF)") (class "Default")
      (node (ref "PCB2") (pin "AREF") (pinfunction "AREF_AREF") (pintype "bidirectional"))
    )
    (net (code "100") (name "unconnected-(PCB2-PadGND...)") (class "Default")
      (node (ref "PCB2") (pin "GND...") (pinfunction "GND..._GND...") (pintype "bidirectional"))
    )
    (net (code "101") (name "unconnected-(PCB2-PadGND....)") (class "Default")
      (node (ref "PCB2") (pin "GND....") (pinfunction "GND...._GND....") (pintype "bidirectional"))
    )
    (net (code "102") (name "unconnected-(PCB2-PadGND__)") (class "Default")
      (node (ref "PCB2") (pin "GND__") (pinfunction "GND___GND__") (pintype "bidirectional"))
    )
    (net (code "103") (name "unconnected-(PCB2-PadMISO)") (class "Default")
      (node (ref "PCB2") (pin "MISO") (pinfunction "MISO_MISO") (pintype "bidirectional"))
    )
    (net (code "104") (name "unconnected-(PCB2-PadMOSI)") (class "Default")
      (node (ref "PCB2") (pin "MOSI") (pinfunction "MOSI_MOSI") (pintype "bidirectional"))
    )
    (net (code "105") (name "unconnected-(PCB2-PadRESET.)") (class "Default")
      (node (ref "PCB2") (pin "RESET.") (pinfunction "RESET._RESET.") (pintype "bidirectional"))
    )
    (net (code "106") (name "unconnected-(PCB2-PadSCK)") (class "Default")
      (node (ref "PCB2") (pin "SCK") (pinfunction "SCK_SCK") (pintype "bidirectional"))
    )
    (net (code "107") (name "unconnected-(PCB2-PadSCL1)") (class "Default")
      (node (ref "PCB2") (pin "SCL1") (pinfunction "SCL1_SCL1") (pintype "bidirectional"))
    )
    (net (code "108") (name "unconnected-(PCB2-PadSDA1)") (class "Default")
      (node (ref "PCB2") (pin "SDA1") (pinfunction "SDA1_SDA1") (pintype "bidirectional"))
    )
  )
)
